# 13_CAN_RS232_485.net
KiCad netlist of a schematic drawn in Altium Designer
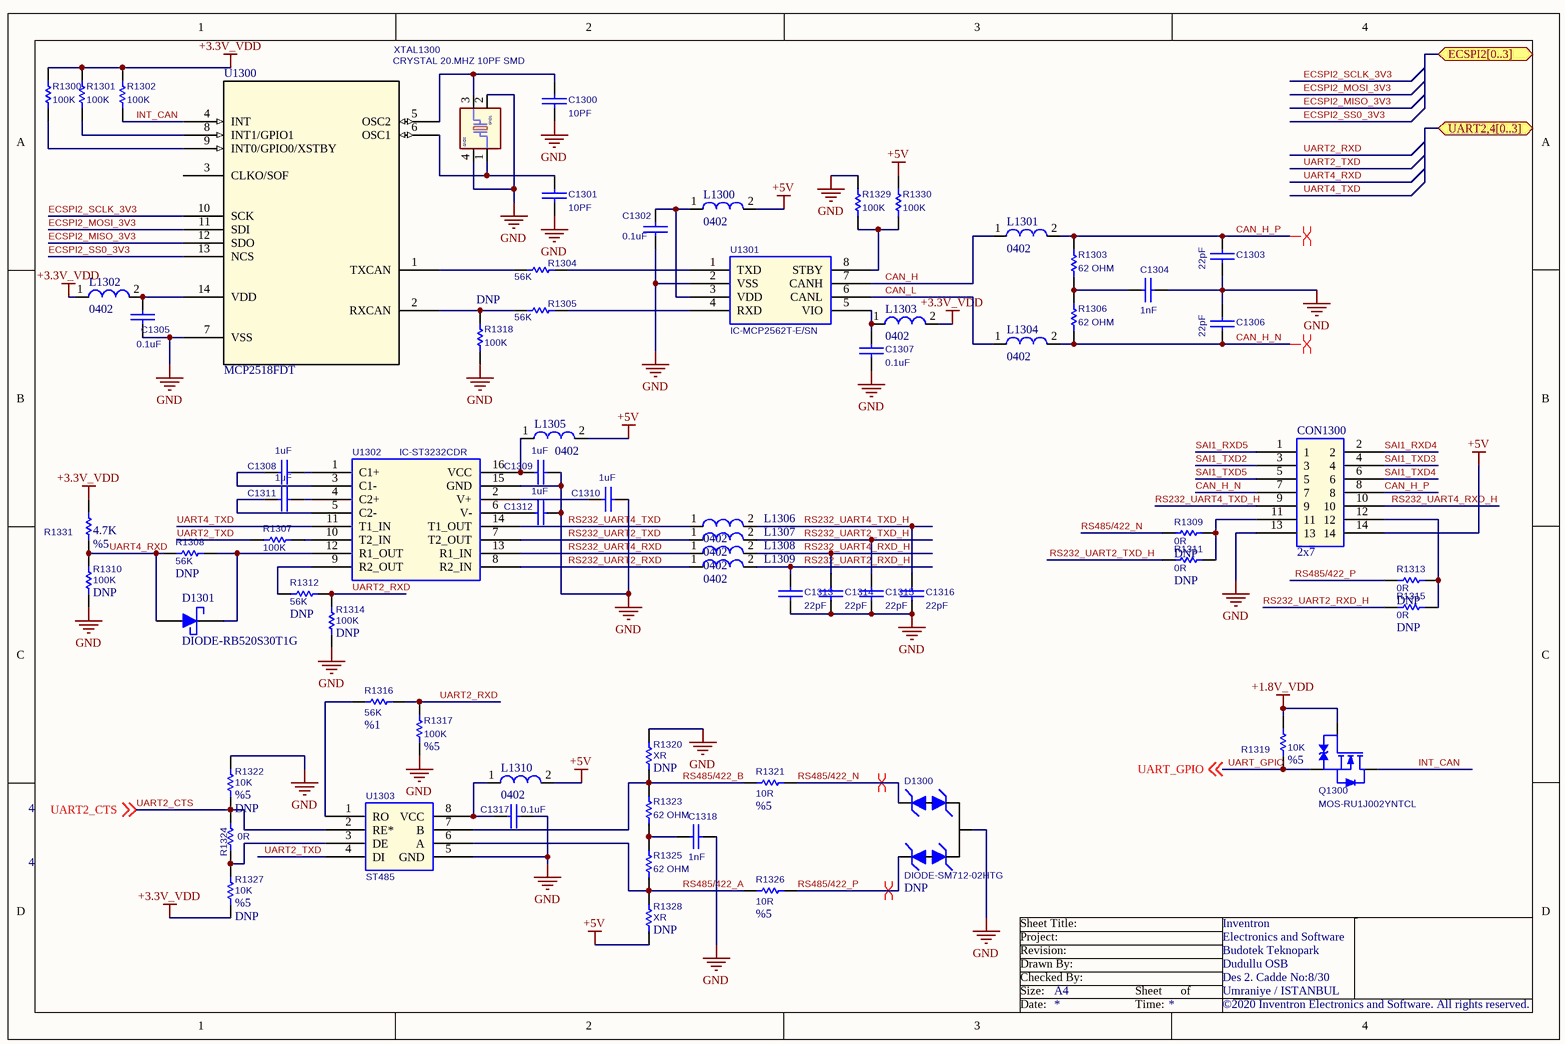
[diagram p0: 13 CAN RS232 485.SchDoc]

(export (version "E")
  (design (tool "Eeschema 10.0.6"))
  (components
    (comp (ref "C1300")
      (value "10PF")
      (footprint "0402_CC")
      (description "CAP CER 10PF 50V C0G/NPO 0402")
      (fields (field (name "CREATED BY") "*") (field (name "CHECKED BY") "*"))
      (libsource (lib "ARETE_SCH") (part "CAP-CC0402JRNPO9BN100"))
    )
    (comp (ref "C1301")
      (value "10PF")
      (footprint "0402_CC")
      (description "CAP CER 10PF 50V C0G/NPO 0402")
      (fields (field (name "CREATED BY") "*") (field (name "CHECKED BY") "*"))
      (libsource (lib "ARETE_SCH") (part "CAP-CC0402JRNPO9BN100"))
    )
    (comp (ref "C1302")
      (value "0.1uF")
      (footprint "0402_CC")
      (description "CAP VER 0.1UF 16V X7R 0402")
      (fields (field (name "CREATED BY") "LA") (field (name "CHECKED BY") "*"))
      (libsource (lib "ARETE_L") (part "CAP-CL05B104KO5NNNC"))
    )
    (comp (ref "C1303")
      (value "22pF")
      (footprint "0402_CC")
      (description "CAP CER 22PF 50V C0G/NPO 0402")
      (fields (field (name "CREATED BY") "LA") (field (name "CHECKED BY") "*"))
      (libsource (lib "ARETE_L") (part "CAP-C0402C220K5GACTU"))
    )
    (comp (ref "C1304")
      (value "1nF")
      (footprint "0603_CC")
      (description "CAP CER 1000PF 100V X7R 0603")
      (fields (field (name "CREATED BY") "LA") (field (name "CHECKED BY") "*"))
      (libsource (lib "ARETE_L") (part "CAP-CGA3E2X7R2A102M080AA"))
    )
    (comp (ref "C1305")
      (value "0.1uF")
      (footprint "0402_CC")
      (description "CAP VER 0.1UF 16V X7R 0402")
      (fields (field (name "CREATED BY") "LA") (field (name "CHECKED BY") "*"))
      (libsource (lib "ARETE_SCH") (part "CAP-CL05B104KO5NNNC"))
    )
    (comp (ref "C1306")
      (value "22pF")
      (footprint "0402_CC")
      (description "CAP CER 22PF 50V C0G/NPO 0402")
      (fields (field (name "CREATED BY") "LA") (field (name "CHECKED BY") "*"))
      (libsource (lib "ARETE_L") (part "CAP-C0402C220K5GACTU"))
    )
    (comp (ref "C1307")
      (value "0.1uF")
      (footprint "0402_CC")
      (description "CAP VER 0.1UF 16V X7R 0402")
      (fields (field (name "CREATED BY") "LA") (field (name "CHECKED BY") "*"))
      (libsource (lib "ARETE_L") (part "CAP-CL05B104KO5NNNC"))
    )
    (comp (ref "C1308")
      (value "1uF")
      (footprint "0603_CC")
      (description "CAP CER 1UF 25V X7R 0603")
      (fields (field (name "CREATED BY") "LA") (field (name "CHECKED BY") "*"))
      (libsource (lib "ARETE_SCH") (part "CAP-CL10B105KA8NNNC"))
    )
    (comp (ref "C1309")
      (value "1uF")
      (footprint "0603_CC")
      (description "CAP CER 1UF 25V X7R 0603")
      (fields (field (name "CREATED BY") "LA") (field (name "CHECKED BY") "*"))
      (libsource (lib "ARETE_SCH") (part "CAP-CL10B105KA8NNNC"))
    )
    (comp (ref "C1310")
      (value "1uF")
      (footprint "0603_CC")
      (description "CAP CER 1UF 25V X7R 0603")
      (fields (field (name "CREATED BY") "LA") (field (name "CHECKED BY") "*"))
      (libsource (lib "ARETE_SCH") (part "CAP-CL10B105KA8NNNC"))
    )
    (comp (ref "C1311")
      (value "1uF")
      (footprint "0603_CC")
      (description "CAP CER 1UF 25V X7R 0603")
      (fields (field (name "CREATED BY") "LA") (field (name "CHECKED BY") "*"))
      (libsource (lib "ARETE_SCH") (part "CAP-CL10B105KA8NNNC"))
    )
    (comp (ref "C1312")
      (value "1uF")
      (footprint "0603_CC")
      (description "CAP CER 1UF 25V X7R 0603")
      (fields (field (name "CREATED BY") "LA") (field (name "CHECKED BY") "*"))
      (libsource (lib "ARETE_SCH") (part "CAP-CL10B105KA8NNNC"))
    )
    (comp (ref "C1313")
      (value "22pF")
      (footprint "0402_CC")
      (description "CAP CER 22PF 50V C0G/NPO 0402")
      (fields (field (name "CREATED BY") "LA") (field (name "CHECKED BY") "*"))
      (libsource (lib "ARETE_L") (part "CAP-C0402C220K5GACTU"))
    )
    (comp (ref "C1314")
      (value "22pF")
      (footprint "0402_CC")
      (description "CAP CER 22PF 50V C0G/NPO 0402")
      (fields (field (name "CREATED BY") "LA") (field (name "CHECKED BY") "*"))
      (libsource (lib "ARETE_L") (part "CAP-C0402C220K5GACTU"))
    )
    (comp (ref "C1315")
      (value "22pF")
      (footprint "0402_CC")
      (description "CAP CER 22PF 50V C0G/NPO 0402")
      (fields (field (name "CREATED BY") "LA") (field (name "CHECKED BY") "*"))
      (libsource (lib "ARETE_L") (part "CAP-C0402C220K5GACTU"))
    )
    (comp (ref "C1316")
      (value "22pF")
      (footprint "0402_CC")
      (description "CAP CER 22PF 50V C0G/NPO 0402")
      (fields (field (name "CREATED BY") "LA") (field (name "CHECKED BY") "*"))
      (libsource (lib "ARETE_L") (part "CAP-C0402C220K5GACTU"))
    )
    (comp (ref "C1317")
      (value "0.1uF")
      (footprint "0402_CC")
      (description "CAP VER 0.1UF 16V X7R 0402")
      (fields (field (name "CREATED BY") "LA") (field (name "CHECKED BY") "*"))
      (libsource (lib "ARETE_L") (part "CAP-CL05B104KO5NNNC"))
    )
    (comp (ref "C1318")
      (value "1nF")
      (footprint "0603_CC")
      (description "CAP CER 1000PF 100V X7R 0603")
      (fields (field (name "CREATED BY") "LA") (field (name "CHECKED BY") "*"))
      (libsource (lib "ARETE_L") (part "CAP-CGA3E2X7R2A102M080AA"))
    )
    (comp (ref "CON1300")
      (value "2x7")
      (footprint "HEADER 2.54 2X7")
      (description "14 PIN 2.54MM HEADER")
      (fields (field (name "CREATED BY") "*") (field (name "CHECKED BY") "*"))
      (libsource (lib "ARETE_SCH") (part "CON-14 PIN 2.54MM"))
    )
    (comp (ref "D1300")
      (value "DIODE-SM712-02HTG")
      (footprint "SOT23")
      (description "TVS DIODE 12V 31V SOT23-3")
      (fields
        (field (name "ASSY_OPT") "DNP")
        (field (name "CREATED BY") "LA")
        (field (name "CHECKED BY") "*")
      )
      (libsource (lib "ARETE_L") (part "DIODE-SM712-02HTG"))
    )
    (comp (ref "D1301")
      (value "DIODE-RB520S30T1G")
      (footprint "SOD523")
      (description "DIODE SCHOTTKY 30V 200MA SOD523")
      (fields (field (name "CREATED BY") "LA") (field (name "CHECKED BY") "*"))
      (libsource (lib "ARETE_L") (part "DIODE-RB520S30T1G"))
    )
    (comp (ref "L1300")
      (value "0402")
      (footprint "0402_RES")
      (description "0OHM 0402")
      (fields (field (name "CREATED BY") "EE") (field (name "CHECKED BY") "*"))
      (libsource (lib "ARETE_SCH") (part "IND-FERRITE (RES 0 OHM) 0402"))
    )
    (comp (ref "L1301")
      (value "0402")
      (footprint "0402_RES")
      (description "0OHM 0402")
      (fields (field (name "CREATED BY") "EE") (field (name "CHECKED BY") "*"))
      (libsource (lib "ARETE_SCH") (part "IND-FERRITE (RES 0 OHM) 0402"))
    )
    (comp (ref "L1302")
      (value "0402")
      (footprint "0402_RES")
      (description "0OHM 0402")
      (fields (field (name "CREATED BY") "EE") (field (name "CHECKED BY") "*"))
      (libsource (lib "ARETE_SCH") (part "IND-FERRITE (RES 0 OHM) 0402"))
    )
    (comp (ref "L1303")
      (value "0402")
      (footprint "0402_RES")
      (description "0OHM 0402")
      (fields (field (name "CREATED BY") "EE") (field (name "CHECKED BY") "*"))
      (libsource (lib "ARETE_SCH") (part "IND-FERRITE (RES 0 OHM) 0402"))
    )
    (comp (ref "L1304")
      (value "0402")
      (footprint "0402_RES")
      (description "0OHM 0402")
      (fields (field (name "CREATED BY") "EE") (field (name "CHECKED BY") "*"))
      (libsource (lib "ARETE_SCH") (part "IND-FERRITE (RES 0 OHM) 0402"))
    )
    (comp (ref "L1305")
      (value "0402")
      (footprint "0402_RES")
      (description "0OHM 0402")
      (fields (field (name "CREATED BY") "EE") (field (name "CHECKED BY") "*"))
      (libsource (lib "ARETE_SCH") (part "IND-FERRITE (RES 0 OHM) 0402"))
    )
    (comp (ref "L1306")
      (value "0402")
      (footprint "0402_RES")
      (description "0OHM 0402")
      (fields (field (name "CREATED BY") "EE") (field (name "CHECKED BY") "*"))
      (libsource (lib "ARETE_SCH") (part "IND-FERRITE (RES 0 OHM) 0402"))
    )
    (comp (ref "L1307")
      (value "0402")
      (footprint "0402_RES")
      (description "0OHM 0402")
      (fields (field (name "CREATED BY") "EE") (field (name "CHECKED BY") "*"))
      (libsource (lib "ARETE_SCH") (part "IND-FERRITE (RES 0 OHM) 0402"))
    )
    (comp (ref "L1308")
      (value "0402")
      (footprint "0402_RES")
      (description "0OHM 0402")
      (fields (field (name "CREATED BY") "EE") (field (name "CHECKED BY") "*"))
      (libsource (lib "ARETE_SCH") (part "IND-FERRITE (RES 0 OHM) 0402"))
    )
    (comp (ref "L1309")
      (value "0402")
      (footprint "0402_RES")
      (description "0OHM 0402")
      (fields (field (name "CREATED BY") "EE") (field (name "CHECKED BY") "*"))
      (libsource (lib "ARETE_SCH") (part "IND-FERRITE (RES 0 OHM) 0402"))
    )
    (comp (ref "L1310")
      (value "0402")
      (footprint "0402_RES")
      (description "0OHM 0402")
      (fields (field (name "CREATED BY") "EE") (field (name "CHECKED BY") "*"))
      (libsource (lib "ARETE_SCH") (part "IND-FERRITE (RES 0 OHM) 0402"))
    )
    (comp (ref "Q1300")
      (value "MOS-RU1J002YNTCL")
      (footprint "SC-85-3/SOT-323FL")
      (description "MOSFET N-CH 50V 0.2A UMT3F")
      (fields (field (name "CREATED BY") "LA") (field (name "CHECKED BY") "*"))
      (libsource (lib "ARETE_L") (part "MOS-RU1J002YNTCL"))
    )
    (comp (ref "R1300")
      (value "100K")
      (footprint "0402_RES")
      (description "RES 100K OHM 5% 1/16W 0402")
      (fields
        (field (name "TOLERANCE") "%5")
        (field (name "CREATED BY") "LA")
        (field (name "CHECKED BY") "*")
      )
      (libsource (lib "ARETE_L") (part "RES-RMCF0402JT100K"))
    )
    (comp (ref "R1301")
      (value "100K")
      (footprint "0402_RES")
      (description "RES 100K OHM 5% 1/16W 0402")
      (fields
        (field (name "TOLERANCE") "%5")
        (field (name "CREATED BY") "LA")
        (field (name "CHECKED BY") "*")
      )
      (libsource (lib "ARETE_L") (part "RES-RMCF0402JT100K"))
    )
    (comp (ref "R1302")
      (value "100K")
      (footprint "0402_RES")
      (description "RES 100K OHM 5% 1/16W 0402")
      (fields
        (field (name "TOLERANCE") "%5")
        (field (name "CREATED BY") "LA")
        (field (name "CHECKED BY") "*")
      )
      (libsource (lib "ARETE_L") (part "RES-RMCF0402JT100K"))
    )
    (comp (ref "R1303")
      (value "62 OHM")
      (footprint "1206")
      (description "62 Ohms ±5% 0.25W, 1/4W Chip Resistor 1206 (3216 Metric) Automotive AEC-Q200 Thick Film")
      (fields (field (name "CREATED BY") "EE") (field (name "CHECKED BY") "*"))
      (libsource (lib "ARETE_SCH") (part "RES-RMCF1206JT62R0"))
    )
    (comp (ref "R1304")
      (value "56K")
      (footprint "0402_RES")
      (description "RES 56K OHM 1% 1/16W 0402")
      (fields
        (field (name "TOLERANCE") "%1")
        (field (name "CREATED BY") "LA")
        (field (name "CHECKED BY") "*")
      )
      (libsource (lib "ARETE_L") (part "RES-56K"))
    )
    (comp (ref "R1305")
      (value "56K")
      (footprint "0402_RES")
      (description "RES 56K OHM 1% 1/16W 0402")
      (fields
        (field (name "TOLERANCE") "%1")
        (field (name "CREATED BY") "LA")
        (field (name "CHECKED BY") "*")
      )
      (libsource (lib "ARETE_L") (part "RES-56K"))
    )
    (comp (ref "R1306")
      (value "62 OHM")
      (footprint "1206")
      (description "62 Ohms ±5% 0.25W, 1/4W Chip Resistor 1206 (3216 Metric) Automotive AEC-Q200 Thick Film")
      (fields (field (name "CREATED BY") "EE") (field (name "CHECKED BY") "*"))
      (libsource (lib "ARETE_SCH") (part "RES-RMCF1206JT62R0"))
    )
    (comp (ref "R1307")
      (value "100K")
      (footprint "0402_RES")
      (description "RES 100K OHM 5% 1/16W 0402")
      (fields
        (field (name "TOLERANCE") "%5")
        (field (name "CREATED BY") "LA")
        (field (name "CHECKED BY") "*")
      )
      (libsource (lib "ARETE_L") (part "RES-RMCF0402JT100K"))
    )
    (comp (ref "R1308")
      (value "56K")
      (footprint "0402_RES")
      (description "RES 56K OHM 1% 1/16W 0402")
      (fields
        (field (name "ASSY_OPT") "DNP")
        (field (name "TOLERANCE") "%1")
        (field (name "CREATED BY") "LA")
        (field (name "CHECKED BY") "*")
      )
      (libsource (lib "ARETE_L") (part "RES-56K"))
    )
    (comp (ref "R1309")
      (value "0R")
      (footprint "0402_RES")
      (description "RES 0 OHM JUMPER 1/16W 0402")
      (fields
        (field (name "ASSY_OPT") "DNP")
        (field (name "CREATED BY") "LA")
        (field (name "CHECKED BY") "*")
      )
      (libsource (lib "ARETE_L") (part "RES-RMCF0402ZT0R00"))
    )
    (comp (ref "R1310")
      (value "100K")
      (footprint "0402_RES")
      (description "RES 100K OHM 5% 1/16W 0402")
      (fields
        (field (name "ASSY_OPT") "DNP")
        (field (name "TOLERANCE") "%5")
        (field (name "CREATED BY") "LA")
        (field (name "CHECKED BY") "*")
      )
      (libsource (lib "ARETE_L") (part "RES-RMCF0402JT100K"))
    )
    (comp (ref "R1311")
      (value "0R")
      (footprint "0402_RES")
      (description "RES 0 OHM JUMPER 1/16W 0402")
      (fields
        (field (name "ASSY_OPT") "DNP")
        (field (name "CREATED BY") "LA")
        (field (name "CHECKED BY") "*")
      )
      (libsource (lib "ARETE_L") (part "RES-RMCF0402ZT0R00"))
    )
    (comp (ref "R1312")
      (value "56K")
      (footprint "0402_RES")
      (description "RES 56K OHM 1% 1/16W 0402")
      (fields
        (field (name "ASSY_OPT") "DNP")
        (field (name "TOLERANCE") "%1")
        (field (name "CREATED BY") "LA")
        (field (name "CHECKED BY") "*")
      )
      (libsource (lib "ARETE_L") (part "RES-56K"))
    )
    (comp (ref "R1313")
      (value "0R")
      (footprint "0402_RES")
      (description "RES 0 OHM JUMPER 1/16W 0402")
      (fields
        (field (name "ASSY_OPT") "DNP")
        (field (name "CREATED BY") "LA")
        (field (name "CHECKED BY") "*")
      )
      (libsource (lib "ARETE_L") (part "RES-RMCF0402ZT0R00"))
    )
    (comp (ref "R1314")
      (value "100K")
      (footprint "0402_RES")
      (description "RES 100K OHM 5% 1/16W 0402")
      (fields
        (field (name "ASSY_OPT") "DNP")
        (field (name "TOLERANCE") "%5")
        (field (name "CREATED BY") "LA")
        (field (name "CHECKED BY") "*")
      )
      (libsource (lib "ARETE_L") (part "RES-RMCF0402JT100K"))
    )
    (comp (ref "R1315")
      (value "0R")
      (footprint "0402_RES")
      (description "RES 0 OHM JUMPER 1/16W 0402")
      (fields
        (field (name "ASSY_OPT") "DNP")
        (field (name "CREATED BY") "LA")
        (field (name "CHECKED BY") "*")
      )
      (libsource (lib "ARETE_L") (part "RES-RMCF0402ZT0R00"))
    )
    (comp (ref "R1316")
      (value "56K")
      (footprint "0402_RES")
      (description "RES 56K OHM 1% 1/16W 0402")
      (fields
        (field (name "TOLERANCE") "%1")
        (field (name "CREATED BY") "LA")
        (field (name "CHECKED BY") "*")
      )
      (libsource (lib "ARETE_L") (part "RES-56K"))
    )
    (comp (ref "R1317")
      (value "100K")
      (footprint "0402_RES")
      (description "RES 100K OHM 5% 1/16W 0402")
      (fields
        (field (name "TOLERANCE") "%5")
        (field (name "CREATED BY") "LA")
        (field (name "CHECKED BY") "*")
      )
      (libsource (lib "ARETE_L") (part "RES-RMCF0402JT100K"))
    )
    (comp (ref "R1318")
      (value "100K")
      (footprint "0402_RES")
      (description "RES 100K OHM 5% 1/16W 0402")
      (fields
        (field (name "ASSY_OPT") "DNP")
        (field (name "TOLERANCE") "%5")
        (field (name "CREATED BY") "LA")
        (field (name "CHECKED BY") "*")
      )
      (libsource (lib "ARETE_L") (part "RES-RMCF0402JT100K"))
    )
    (comp (ref "R1319")
      (value "10K")
      (footprint "0402_RES")
      (description "RES 10K OHM 5% 1/16W 0402")
      (fields
        (field (name "TOLERANCE") "%5")
        (field (name "CREATED BY") "LA")
        (field (name "CHECKED BY") "*")
      )
      (libsource (lib "ARETE_SCH") (part "RES-RMCF0402JT10K0"))
    )
    (comp (ref "R1320")
      (value "XR")
      (footprint "0603_RES")
      (description "RES")
      (fields
        (field (name "ASSY_OPT") "DNP")
        (field (name "CREATED BY") "LA")
        (field (name "CHECKED BY") "*")
      )
      (libsource (lib "ARETE_L") (part "RES-0R 0603"))
    )
    (comp (ref "R1321")
      (value "10R")
      (footprint "0402_RES")
      (description "RES 10 OHM 5% 1/16W 0402")
      (fields
        (field (name "TOLERANCE") "%5")
        (field (name "CREATED BY") "LA")
        (field (name "CHECKED BY") "*")
      )
      (libsource (lib "ARETE_L") (part "RES-RMCF0402JT10R0"))
    )
    (comp (ref "R1322")
      (value "10K")
      (footprint "0402_RES")
      (description "RES 10K OHM 5% 1/16W 0402")
      (fields
        (field (name "TOLERANCE") "%5")
        (field (name "ASSY_OPT") "DNP")
        (field (name "CREATED BY") "LA")
        (field (name "CHECKED BY") "*")
      )
      (libsource (lib "ARETE_L") (part "RES-RMCF0402JT10K0"))
    )
    (comp (ref "R1323")
      (value "62 OHM")
      (footprint "1206")
      (description "62 Ohms ±5% 0.25W, 1/4W Chip Resistor 1206 (3216 Metric) Automotive AEC-Q200 Thick Film")
      (fields (field (name "CREATED BY") "EE") (field (name "CHECKED BY") "*"))
      (libsource (lib "ARETE_SCH") (part "RES-RMCF1206JT62R0"))
    )
    (comp (ref "R1324")
      (value "0R")
      (footprint "0402_RES")
      (description "RES 0 OHM JUMPER 1/16W 0402")
      (fields (field (name "CREATED BY") "LA") (field (name "CHECKED BY") "*"))
      (libsource (lib "ARETE_L") (part "RES-RMCF0402ZT0R00"))
    )
    (comp (ref "R1325")
      (value "62 OHM")
      (footprint "1206")
      (description "62 Ohms ±5% 0.25W, 1/4W Chip Resistor 1206 (3216 Metric) Automotive AEC-Q200 Thick Film")
      (fields (field (name "CREATED BY") "EE") (field (name "CHECKED BY") "*"))
      (libsource (lib "ARETE_SCH") (part "RES-RMCF1206JT62R0"))
    )
    (comp (ref "R1326")
      (value "10R")
      (footprint "0402_RES")
      (description "RES 10 OHM 5% 1/16W 0402")
      (fields
        (field (name "TOLERANCE") "%5")
        (field (name "CREATED BY") "LA")
        (field (name "CHECKED BY") "*")
      )
      (libsource (lib "ARETE_L") (part "RES-RMCF0402JT10R0"))
    )
    (comp (ref "R1327")
      (value "10K")
      (footprint "0402_RES")
      (description "RES 10K OHM 5% 1/16W 0402")
      (fields
        (field (name "TOLERANCE") "%5")
        (field (name "ASSY_OPT") "DNP")
        (field (name "CREATED BY") "LA")
        (field (name "CHECKED BY") "*")
      )
      (libsource (lib "ARETE_L") (part "RES-RMCF0402JT10K0"))
    )
    (comp (ref "R1328")
      (value "XR")
      (footprint "0603_RES")
      (description "RES")
      (fields
        (field (name "ASSY_OPT") "DNP")
        (field (name "CREATED BY") "LA")
        (field (name "CHECKED BY") "*")
      )
      (libsource (lib "ARETE_L") (part "RES-0R 0603"))
    )
    (comp (ref "R1329")
      (value "100K")
      (footprint "0402_RES")
      (description "RES 100K OHM 5% 1/16W 0402")
      (fields
        (field (name "TOLERANCE") "%5")
        (field (name "CREATED BY") "LA")
        (field (name "CHECKED BY") "*")
      )
      (libsource (lib "ARETE_L") (part "RES-RMCF0402JT100K"))
    )
    (comp (ref "R1330")
      (value "100K")
      (footprint "0402_RES")
      (description "RES 100K OHM 5% 1/16W 0402")
      (fields
        (field (name "TOLERANCE") "%5")
        (field (name "CREATED BY") "LA")
        (field (name "CHECKED BY") "*")
      )
      (libsource (lib "ARETE_L") (part "RES-RMCF0402JT100K"))
    )
    (comp (ref "R1331")
      (value "4.7K")
      (footprint "0402_RES")
      (description "RES 4.7K OHM 5% 1/16W 0402")
      (fields
        (field (name "TOLERANCE") "%5")
        (field (name "CREATED BY") "LA")
        (field (name "CHECKED BY") "*")
      )
      (libsource (lib "ARETE_SCH") (part "RES-4.7K"))
    )
    (comp (ref "U1300")
      (value "MCP2518FDT")
      (footprint "SOIC-14")
      (description "CAN Controller CAN 2.0 SPI Interface 14-SOIC")
      (fields (field (name "CREATED BY") "EE") (field (name "CHECKED BY") "*"))
      (libsource (lib "ARETE_SCH") (part "IC-MCP2518FDT-E/SL"))
    )
    (comp (ref "U1301")
      (value "IC-MCP2562T-E/SN")
      (footprint "8-SOIC/FAN3229")
      (description "IC TXRX CAN 8SOIC")
      (fields (field (name "CREATED BY") "LA") (field (name "CHECKED BY") "*"))
      (libsource (lib "ARETE_SCH") (part "IC-MCP2562T-E/SN"))
    )
    (comp (ref "U1302")
      (value "IC-ST3232CDR")
      (footprint "SO-16")
      (description "IC TX/RX 3-3.5V RS232 LP 16-SOIC")
      (fields (field (name "CREATED BY") "LA") (field (name "CHECKED BY") "*"))
      (libsource (lib "ARETE_L") (part "IC-ST3232CDR"))
    )
    (comp (ref "U1303")
      (value "ST485")
      (footprint "8-SOIC/FAN3229")
      (description "IC TXRX LOPWR RS485/422 8 SOIC")
      (fields (field (name "CREATED BY") "LA") (field (name "CHECKED BY") "*"))
      (libsource (lib "ARETE_L") (part "IC-ST485EBDR"))
    )
    (comp (ref "XTAL1300")
      (value "CRYSTAL 20.MHZ 10PF SMD")
      (footprint "XTLOSC4_3P2X2P5MM_SM")
      (description "CRYSTAL 20.0000MHZ 10PF SMD")
      (fields (field (name "CREATED BY") "E.E") (field (name "CHECKED BY") "*"))
      (libsource (lib "ARETE_SCH") (part "XTAL-FA-238 20.0000MB-K0"))
    )
  )
  (nets
    (net (code "9") (name "+1.8V_VDD") (class "Default")
      (node (ref "Q1300") (pin "1") (pinfunction "G_1") (pintype "passive"))
      (node (ref "R1319") (pin "1") (pinfunction "1_1") (pintype "passive"))
    )
    (net (code "10") (name "+3.3V_VDD") (class "Default")
      (node (ref "L1302") (pin "1") (pinfunction "1_1") (pintype "passive"))
      (node (ref "L1303") (pin "2") (pinfunction "2_2") (pintype "passive"))
      (node (ref "R1300") (pin "2") (pinfunction "2_2") (pintype "passive"))
      (node (ref "R1301") (pin "2") (pinfunction "2_2") (pintype "passive"))
      (node (ref "R1302") (pin "2") (pinfunction "2_2") (pintype "passive"))
      (node (ref "R1327") (pin "1") (pinfunction "1_1") (pintype "passive"))
      (node (ref "R1331") (pin "2") (pinfunction "2_2") (pintype "passive"))
    )
    (net (code "11") (name "+5V") (class "Default")
      (node (ref "CON1300") (pin "14") (pinfunction "14_14") (pintype "passive"))
      (node (ref "L1300") (pin "2") (pinfunction "2_2") (pintype "passive"))
      (node (ref "L1305") (pin "2") (pinfunction "2_2") (pintype "passive"))
      (node (ref "L1310") (pin "2") (pinfunction "2_2") (pintype "passive"))
      (node (ref "R1328") (pin "1") (pinfunction "1_1") (pintype "passive"))
      (node (ref "R1330") (pin "2") (pinfunction "2_2") (pintype "passive"))
    )
    (net (code "12") (name "/CAN_H") (class "Default")
      (node (ref "L1301") (pin "1") (pinfunction "1_1") (pintype "passive"))
      (node (ref "U1301") (pin "7") (pinfunction "CANH_7") (pintype "passive"))
    )
    (net (code "13") (name "/CAN_H_N") (class "Default")
      (node (ref "C1306") (pin "2") (pinfunction "2_2") (pintype "passive"))
      (node (ref "CON1300") (pin "7") (pinfunction "7_7") (pintype "passive"))
      (node (ref "L1304") (pin "2") (pinfunction "2_2") (pintype "passive"))
      (node (ref "R1306") (pin "1") (pinfunction "1_1") (pintype "passive"))
    )
    (net (code "14") (name "/CAN_H_P") (class "Default")
      (node (ref "C1303") (pin "1") (pinfunction "1_1") (pintype "passive"))
      (node (ref "CON1300") (pin "8") (pinfunction "8_8") (pintype "passive"))
      (node (ref "L1301") (pin "2") (pinfunction "2_2") (pintype "passive"))
      (node (ref "R1303") (pin "2") (pinfunction "2_2") (pintype "passive"))
    )
    (net (code "15") (name "/CAN_L") (class "Default")
      (node (ref "L1304") (pin "1") (pinfunction "1_1") (pintype "passive"))
      (node (ref "U1301") (pin "6") (pinfunction "CANL_6") (pintype "passive"))
    )
    (net (code "17") (name "/ECSPI2_MISO_3V3") (class "Default")
      (node (ref "U1300") (pin "12") (pinfunction "SDO_12") (pintype "passive"))
    )
    (net (code "18") (name "/ECSPI2_MOSI_3V3") (class "Default")
      (node (ref "U1300") (pin "11") (pinfunction "SDI_11") (pintype "passive"))
    )
    (net (code "19") (name "/ECSPI2_SCLK_3V3") (class "Default")
      (node (ref "U1300") (pin "10") (pinfunction "SCK_10") (pintype "passive"))
    )
    (net (code "20") (name "/ECSPI2_SS0_3V3") (class "Default")
      (node (ref "U1300") (pin "13") (pinfunction "NCS_13") (pintype "passive"))
    )
    (net (code "21") (name "/INT_CAN") (class "Default")
      (node (ref "Q1300") (pin "3") (pinfunction "D_3") (pintype "passive"))
      (node (ref "R1302") (pin "1") (pinfunction "1_1") (pintype "passive"))
      (node (ref "U1300") (pin "4") (pinfunction "INT_4") (pintype "input"))
    )
    (net (code "22") (name "/RS232_UART2_RXD") (class "Default")
      (node (ref "L1309") (pin "1") (pinfunction "1_1") (pintype "passive"))
      (node (ref "U1302") (pin "8") (pinfunction "R2_IN_8") (pintype "passive"))
    )
    (net (code "23") (name "/RS232_UART2_RXD_H") (class "Default")
      (node (ref "C1313") (pin "1") (pinfunction "1_1") (pintype "passive"))
      (node (ref "L1309") (pin "2") (pinfunction "2_2") (pintype "passive"))
      (node (ref "R1315") (pin "1") (pinfunction "1_1") (pintype "passive"))
    )
    (net (code "24") (name "/RS232_UART2_TXD") (class "Default")
      (node (ref "L1307") (pin "1") (pinfunction "1_1") (pintype "passive"))
      (node (ref "U1302") (pin "7") (pinfunction "T2_OUT_7") (pintype "passive"))
    )
    (net (code "25") (name "/RS232_UART2_TXD_H") (class "Default")
      (node (ref "C1315") (pin "1") (pinfunction "1_1") (pintype "passive"))
      (node (ref "L1307") (pin "2") (pinfunction "2_2") (pintype "passive"))
      (node (ref "R1311") (pin "1") (pinfunction "1_1") (pintype "passive"))
    )
    (net (code "26") (name "/RS232_UART4_RXD") (class "Default")
      (node (ref "L1308") (pin "1") (pinfunction "1_1") (pintype "passive"))
      (node (ref "U1302") (pin "13") (pinfunction "R1_IN_13") (pintype "passive"))
    )
    (net (code "27") (name "/RS232_UART4_RXD_H") (class "Default")
      (node (ref "C1314") (pin "1") (pinfunction "1_1") (pintype "passive"))
      (node (ref "CON1300") (pin "10") (pinfunction "10_10") (pintype "passive"))
      (node (ref "L1308") (pin "2") (pinfunction "2_2") (pintype "passive"))
    )
    (net (code "28") (name "/RS232_UART4_TXD") (class "Default")
      (node (ref "L1306") (pin "1") (pinfunction "1_1") (pintype "passive"))
      (node (ref "U1302") (pin "14") (pinfunction "T1_OUT_14") (pintype "passive"))
    )
    (net (code "29") (name "/RS232_UART4_TXD_H") (class "Default")
      (node (ref "C1316") (pin "1") (pinfunction "1_1") (pintype "passive"))
      (node (ref "CON1300") (pin "9") (pinfunction "9_9") (pintype "passive"))
      (node (ref "L1306") (pin "2") (pinfunction "2_2") (pintype "passive"))
    )
    (net (code "30") (name "/RS485{slash}422_A") (class "Default")
      (node (ref "R1325") (pin "1") (pinfunction "1_1") (pintype "passive"))
      (node (ref "R1326") (pin "1") (pinfunction "1_1") (pintype "passive"))
      (node (ref "R1328") (pin "2") (pinfunction "2_2") (pintype "passive"))
      (node (ref "U1303") (pin "6") (pinfunction "A_6") (pintype "passive"))
    )
    (net (code "31") (name "/RS485{slash}422_B") (class "Default")
      (node (ref "R1320") (pin "2") (pinfunction "2_2") (pintype "passive"))
      (node (ref "R1321") (pin "1") (pinfunction "1_1") (pintype "passive"))
      (node (ref "R1323") (pin "2") (pinfunction "2_2") (pintype "passive"))
      (node (ref "U1303") (pin "7") (pinfunction "B_7") (pintype "passive"))
    )
    (net (code "32") (name "/RS485{slash}422_N") (class "Default")
      (node (ref "D1300") (pin "1") (pinfunction "1_1") (pintype "passive"))
      (node (ref "R1309") (pin "1") (pinfunction "1_1") (pintype "passive"))
      (node (ref "R1321") (pin "2") (pinfunction "2_2") (pintype "passive"))
    )
    (net (code "33") (name "/RS485{slash}422_P") (class "Default")
      (node (ref "D1300") (pin "2") (pinfunction "2_2") (pintype "passive"))
      (node (ref "R1313") (pin "1") (pinfunction "1_1") (pintype "passive"))
      (node (ref "R1326") (pin "2") (pinfunction "2_2") (pintype "passive"))
    )
    (net (code "34") (name "/SAI1_RXD4") (class "Default")
      (node (ref "CON1300") (pin "2") (pinfunction "2_2") (pintype "passive"))
    )
    (net (code "35") (name "/SAI1_RXD5") (class "Default")
      (node (ref "CON1300") (pin "1") (pinfunction "1_1") (pintype "passive"))
    )
    (net (code "36") (name "/SAI1_TXD2") (class "Default")
      (node (ref "CON1300") (pin "3") (pinfunction "3_3") (pintype "passive"))
    )
    (net (code "37") (name "/SAI1_TXD3") (class "Default")
      (node (ref "CON1300") (pin "4") (pinfunction "4_4") (pintype "passive"))
    )
    (net (code "38") (name "/SAI1_TXD4") (class "Default")
      (node (ref "CON1300") (pin "6") (pinfunction "6_6") (pintype "passive"))
    )
    (net (code "39") (name "/SAI1_TXD5") (class "Default")
      (node (ref "CON1300") (pin "5") (pinfunction "5_5") (pintype "passive"))
    )
    (net (code "41") (name "/UART2_RXD") (class "Default")
      (node (ref "R1312") (pin "2") (pinfunction "2_2") (pintype "passive"))
      (node (ref "R1314") (pin "2") (pinfunction "2_2") (pintype "passive"))
      (node (ref "R1316") (pin "1") (pinfunction "1_1") (pintype "passive"))
      (node (ref "R1317") (pin "1") (pinfunction "1_1") (pintype "passive"))
    )
    (net (code "42") (name "/UART2_TXD") (class "Default")
      (node (ref "R1307") (pin "2") (pinfunction "2_2") (pintype "passive"))
      (node (ref "U1303") (pin "4") (pinfunction "DI_4") (pintype "passive"))
    )
    (net (code "43") (name "/UART4_RXD") (class "Default")
      (node (ref "D1301") (pin "1") (pinfunction "A_1") (pintype "passive"))
      (node (ref "R1308") (pin "1") (pinfunction "1_1") (pintype "passive"))
      (node (ref "R1310") (pin "2") (pinfunction "2_2") (pintype "passive"))
      (node (ref "R1331") (pin "1") (pinfunction "1_1") (pintype "passive"))
    )
    (net (code "44") (name "/UART4_TXD") (class "Default")
      (node (ref "U1302") (pin "11") (pinfunction "T1_IN_11") (pintype "passive"))
    )
    (net (code "45") (name "GND") (class "Default")
      (node (ref "C1300") (pin "2") (pinfunction "2_2") (pintype "passive"))
      (node (ref "C1301") (pin "2") (pinfunction "2_2") (pintype "passive"))
      (node (ref "C1302") (pin "1") (pinfunction "1_1") (pintype "passive"))
      (node (ref "C1303") (pin "2") (pinfunction "2_2") (pintype "passive"))
      (node (ref "C1304") (pin "2") (pinfunction "2_2") (pintype "passive"))
      (node (ref "C1305") (pin "2") (pinfunction "2_2") (pintype "passive"))
      (node (ref "C1306") (pin "1") (pinfunction "1_1") (pintype "passive"))
      (node (ref "C1307") (pin "1") (pinfunction "1_1") (pintype "passive"))
      (node (ref "C1309") (pin "2") (pinfunction "2_2") (pintype "passive"))
      (node (ref "C1310") (pin "2") (pinfunction "2_2") (pintype "passive"))
      (node (ref "C1312") (pin "2") (pinfunction "2_2") (pintype "passive"))
      (node (ref "C1313") (pin "2") (pinfunction "2_2") (pintype "passive"))
      (node (ref "C1314") (pin "2") (pinfunction "2_2") (pintype "passive"))
      (node (ref "C1315") (pin "2") (pinfunction "2_2") (pintype "passive"))
      (node (ref "C1316") (pin "2") (pinfunction "2_2") (pintype "passive"))
      (node (ref "C1317") (pin "2") (pinfunction "2_2") (pintype "passive"))
      (node (ref "C1318") (pin "2") (pinfunction "2_2") (pintype "passive"))
      (node (ref "CON1300") (pin "13") (pinfunction "13_13") (pintype "passive"))
      (node (ref "D1300") (pin "3") (pinfunction "3_3") (pintype "passive"))
      (node (ref "R1310") (pin "1") (pinfunction "1_1") (pintype "passive"))
      (node (ref "R1314") (pin "1") (pinfunction "1_1") (pintype "passive"))
      (node (ref "R1317") (pin "2") (pinfunction "2_2") (pintype "passive"))
      (node (ref "R1318") (pin "1") (pinfunction "1_1") (pintype "passive"))
      (node (ref "R1320") (pin "1") (pinfunction "1_1") (pintype "passive"))
      (node (ref "R1322") (pin "2") (pinfunction "2_2") (pintype "passive"))
      (node (ref "R1329") (pin "2") (pinfunction "2_2") (pintype "passive"))
      (node (ref "U1300") (pin "7") (pinfunction "VSS_7") (pintype "passive"))
      (node (ref "U1301") (pin "2") (pinfunction "VSS_2") (pintype "passive"))
      (node (ref "U1302") (pin "15") (pinfunction "GND_15") (pintype "passive"))
      (node (ref "U1303") (pin "5") (pinfunction "GND_5") (pintype "passive"))
      (node (ref "XTAL1300") (pin "2") (pinfunction "GND1_2") (pintype "power_in"))
      (node (ref "XTAL1300") (pin "4") (pinfunction "GND2_4") (pintype "power_in"))
    )
    (net (code "46") (name "Net-(C1304-Pad1)") (class "Default")
      (node (ref "C1304") (pin "1") (pinfunction "1_1") (pintype "passive"))
      (node (ref "R1303") (pin "1") (pinfunction "1_1") (pintype "passive"))
      (node (ref "R1306") (pin "2") (pinfunction "2_2") (pintype "passive"))
    )
    (net (code "47") (name "Net-(C1318-Pad1)") (class "Default")
      (node (ref "C1318") (pin "1") (pinfunction "1_1") (pintype "passive"))
      (node (ref "R1323") (pin "1") (pinfunction "1_1") (pintype "passive"))
      (node (ref "R1325") (pin "2") (pinfunction "2_2") (pintype "passive"))
    )
    (net (code "48") (name "Net-(CON1300-Pad11)") (class "Default")
      (node (ref "CON1300") (pin "11") (pinfunction "11_11") (pintype "passive"))
      (node (ref "R1309") (pin "2") (pinfunction "2_2") (pintype "passive"))
      (node (ref "R1311") (pin "2") (pinfunction "2_2") (pintype "passive"))
    )
    (net (code "49") (name "Net-(CON1300-Pad12)") (class "Default")
      (node (ref "CON1300") (pin "12") (pinfunction "12_12") (pintype "passive"))
      (node (ref "R1313") (pin "2") (pinfunction "2_2") (pintype "passive"))
      (node (ref "R1315") (pin "2") (pinfunction "2_2") (pintype "passive"))
    )
    (net (code "50") (name "Net-(D1301-K)") (class "Default")
      (node (ref "D1301") (pin "2") (pinfunction "K_2") (pintype "passive"))
      (node (ref "R1308") (pin "2") (pinfunction "2_2") (pintype "passive"))
      (node (ref "U1302") (pin "12") (pinfunction "R1_OUT_12") (pintype "passive"))
    )
    (net (code "51") (name "Net-(U1300-INT0{slash}GPIO0{slash}XSTBY)") (class "Default")
      (node (ref "R1300") (pin "1") (pinfunction "1_1") (pintype "passive"))
      (node (ref "U1300") (pin "9") (pinfunction "INT0/GPIO0/XSTBY_9") (pintype "input"))
    )
    (net (code "52") (name "Net-(U1300-INT1{slash}GPIO1)") (class "Default")
      (node (ref "R1301") (pin "1") (pinfunction "1_1") (pintype "passive"))
      (node (ref "U1300") (pin "8") (pinfunction "INT1/GPIO1_8") (pintype "input"))
    )
    (net (code "53") (name "Net-(U1300-OSC1)") (class "Default")
      (node (ref "C1301") (pin "1") (pinfunction "1_1") (pintype "passive"))
      (node (ref "U1300") (pin "6") (pinfunction "OSC1_6") (pintype "bidirectional"))
      (node (ref "XTAL1300") (pin "1") (pinfunction "1_1") (pintype "passive"))
    )
    (net (code "54") (name "Net-(U1300-OSC2)") (class "Default")
      (node (ref "C1300") (pin "1") (pinfunction "1_1") (pintype "passive"))
      (node (ref "U1300") (pin "5") (pinfunction "OSC2_5") (pintype "bidirectional"))
      (node (ref "XTAL1300") (pin "3") (pinfunction "3_3") (pintype "passive"))
    )
    (net (code "55") (name "Net-(U1300-RXCAN)") (class "Default")
      (node (ref "R1305") (pin "1") (pinfunction "1_1") (pintype "passive"))
      (node (ref "R1318") (pin "2") (pinfunction "2_2") (pintype "passive"))
      (node (ref "U1300") (pin "2") (pinfunction "RXCAN_2") (pintype "passive"))
    )
    (net (code "56") (name "Net-(U1300-TXCAN)") (class "Default")
      (node (ref "R1304") (pin "1") (pinfunction "1_1") (pintype "passive"))
      (node (ref "U1300") (pin "1") (pinfunction "TXCAN_1") (pintype "passive"))
    )
    (net (code "57") (name "Net-(U1300-VDD)") (class "Default")
      (node (ref "C1305") (pin "1") (pinfunction "1_1") (pintype "passive"))
      (node (ref "L1302") (pin "2") (pinfunction "2_2") (pintype "passive"))
      (node (ref "U1300") (pin "14") (pinfunction "VDD_14") (pintype "power_in"))
    )
    (net (code "58") (name "Net-(U1301-RXD)") (class "Default")
      (node (ref "R1305") (pin "2") (pinfunction "2_2") (pintype "passive"))
      (node (ref "U1301") (pin "4") (pinfunction "RXD_4") (pintype "passive"))
    )
    (net (code "59") (name "Net-(U1301-STBY)") (class "Default")
      (node (ref "R1329") (pin "1") (pinfunction "1_1") (pintype "passive"))
      (node (ref "R1330") (pin "1") (pinfunction "1_1") (pintype "passive"))
      (node (ref "U1301") (pin "8") (pinfunction "STBY_8") (pintype "passive"))
    )
    (net (code "60") (name "Net-(U1301-TXD)") (class "Default")
      (node (ref "R1304") (pin "2") (pinfunction "2_2") (pintype "passive"))
      (node (ref "U1301") (pin "1") (pinfunction "TXD_1") (pintype "passive"))
    )
    (net (code "61") (name "Net-(U1301-VDD)") (class "Default")
      (node (ref "C1302") (pin "2") (pinfunction "2_2") (pintype "passive"))
      (node (ref "L1300") (pin "1") (pinfunction "1_1") (pintype "passive"))
      (node (ref "U1301") (pin "3") (pinfunction "VDD_3") (pintype "passive"))
    )
    (net (code "62") (name "Net-(U1301-VIO)") (class "Default")
      (node (ref "C1307") (pin "2") (pinfunction "2_2") (pintype "passive"))
      (node (ref "L1303") (pin "1") (pinfunction "1_1") (pintype "passive"))
      (node (ref "U1301") (pin "5") (pinfunction "VIO_5") (pintype "passive"))
    )
    (net (code "63") (name "Net-(U1302-C1+)") (class "Default")
      (node (ref "C1308") (pin "2") (pinfunction "2_2") (pintype "passive"))
      (node (ref "U1302") (pin "1") (pinfunction "C1+_1") (pintype "passive"))
    )
    (net (code "64") (name "Net-(U1302-C1-)") (class "Default")
      (node (ref "C1308") (pin "1") (pinfunction "1_1") (pintype "passive"))
      (node (ref "U1302") (pin "3") (pinfunction "C1-_3") (pintype "passive"))
    )
    (net (code "65") (name "Net-(U1302-C2+)") (class "Default")
      (node (ref "C1311") (pin "2") (pinfunction "2_2") (pintype "passive"))
      (node (ref "U1302") (pin "4") (pinfunction "C2+_4") (pintype "passive"))
    )
    (net (code "66") (name "Net-(U1302-C2-)") (class "Default")
      (node (ref "C1311") (pin "1") (pinfunction "1_1") (pintype "passive"))
      (node (ref "U1302") (pin "5") (pinfunction "C2-_5") (pintype "passive"))
    )
    (net (code "67") (name "Net-(U1302-R2_OUT)") (class "Default")
      (node (ref "R1312") (pin "1") (pinfunction "1_1") (pintype "passive"))
      (node (ref "U1302") (pin "9") (pinfunction "R2_OUT_9") (pintype "passive"))
    )
    (net (code "68") (name "Net-(U1302-T2_IN)") (class "Default")
      (node (ref "R1307") (pin "1") (pinfunction "1_1") (pintype "passive"))
      (node (ref "U1302") (pin "10") (pinfunction "T2_IN_10") (pintype "passive"))
    )
    (net (code "69") (name "Net-(U1302-V+)") (class "Default")
      (node (ref "C1310") (pin "1") (pinfunction "1_1") (pintype "passive"))
      (node (ref "U1302") (pin "2") (pinfunction "V+_2") (pintype "passive"))
    )
    (net (code "70") (name "Net-(U1302-V-)") (class "Default")
      (node (ref "C1312") (pin "1") (pinfunction "1_1") (pintype "passive"))
      (node (ref "U1302") (pin "6") (pinfunction "V-_6") (pintype "passive"))
    )
    (net (code "71") (name "Net-(U1302-VCC)") (class "Default")
      (node (ref "C1309") (pin "1") (pinfunction "1_1") (pintype "passive"))
      (node (ref "L1305") (pin "1") (pinfunction "1_1") (pintype "passive"))
      (node (ref "U1302") (pin "16") (pinfunction "VCC_16") (pintype "passive"))
    )
    (net (code "72") (name "Net-(U1303-DE)") (class "Default")
      (node (ref "R1324") (pin "1") (pinfunction "1_1") (pintype "passive"))
      (node (ref "R1327") (pin "2") (pinfunction "2_2") (pintype "passive"))
      (node (ref "U1303") (pin "3") (pinfunction "DE_3") (pintype "passive"))
    )
    (net (code "73") (name "Net-(U1303-RO)") (class "Default")
      (node (ref "R1316") (pin "2") (pinfunction "2_2") (pintype "passive"))
      (node (ref "U1303") (pin "1") (pinfunction "RO_1") (pintype "passive"))
    )
    (net (code "74") (name "Net-(U1303-VCC)") (class "Default")
      (node (ref "C1317") (pin "1") (pinfunction "1_1") (pintype "passive"))
      (node (ref "L1310") (pin "1") (pinfunction "1_1") (pintype "passive"))
      (node (ref "U1303") (pin "8") (pinfunction "VCC_8") (pintype "passive"))
    )
    (net (code "75") (name "UART2_CTS") (class "Default")
      (node (ref "R1322") (pin "1") (pinfunction "1_1") (pintype "passive"))
      (node (ref "R1324") (pin "2") (pinfunction "2_2") (pintype "passive"))
      (node (ref "U1303") (pin "2") (pinfunction "RE*_2") (pintype "passive"))
    )
    (net (code "76") (name "UART_GPIO") (class "Default")
      (node (ref "Q1300") (pin "2") (pinfunction "S_2") (pintype "passive"))
      (node (ref "R1319") (pin "2") (pinfunction "2_2") (pintype "passive"))
    )
    (net (code "77") (name "unconnected-(U1300-CLKO{slash}SOF-Pad3)") (class "Default")
      (node (ref "U1300") (pin "3") (pinfunction "CLKO/SOF_3") (pintype "passive"))
    )
  )
)
